# regulateur.net
KiCad netlist of a schematic drawn in EAGLE
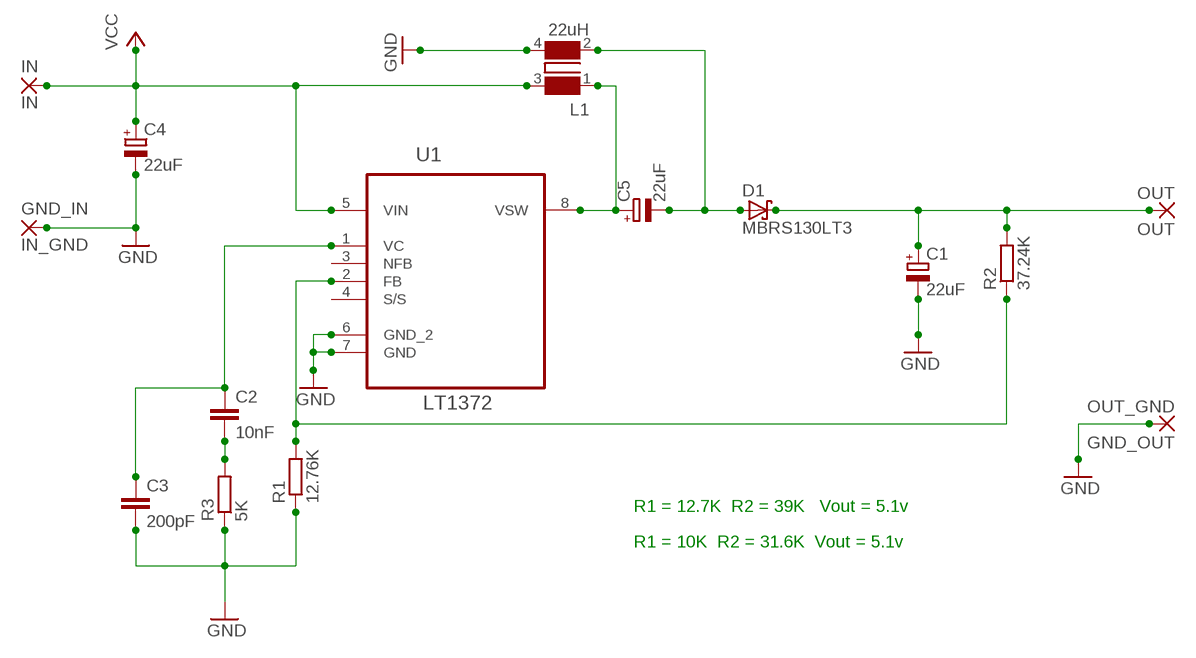
[diagram p0: schematic, sheet 1]

(export (version "E")
  (design (tool "Eeschema 10.0.6"))
  (components
    (comp (ref "C1")
      (value "22uF")
      (footprint "eagle-import:CT7343")
      (libsource (lib "eagle-import") (part "CPOL-EUCT7343"))
    )
    (comp (ref "C2")
      (value "10nF")
      (footprint "eagle-import:C1206")
      (libsource (lib "eagle-import") (part "C-EUC1206"))
    )
    (comp (ref "C3")
      (value "200pF")
      (footprint "eagle-import:C1206")
      (libsource (lib "eagle-import") (part "C-EUC1206"))
    )
    (comp (ref "C4")
      (value "22uF")
      (footprint "eagle-import:CT7343")
      (libsource (lib "eagle-import") (part "CPOL-EUCT7343"))
    )
    (comp (ref "C5")
      (value "22uF")
      (footprint "eagle-import:CT7343")
      (libsource (lib "eagle-import") (part "CPOL-EUCT7343"))
    )
    (comp (ref "D1")
      (value "MBRS130LT3")
      (footprint "eagle-import:SMB")
      (libsource (lib "eagle-import") (part "MBRS130LT3"))
    )
    (comp (ref "GND_IN")
      (value "IN_GND")
      (footprint "eagle-import:3,81_1,3")
      (libsource (lib "eagle-import") (part "3,81/1,3"))
    )
    (comp (ref "GND_OUT")
      (value "OUT_GND")
      (footprint "eagle-import:3,81_1,3")
      (libsource (lib "eagle-import") (part "3,81/1,3"))
    )
    (comp (ref "IN")
      (value "IN")
      (footprint "eagle-import:3,81_1,3")
      (libsource (lib "eagle-import") (part "3,81/1,3"))
    )
    (comp (ref "L1")
      (value "22uH")
      (footprint "eagle-import:WE-DD_12XX_CROSSED")
      (fields (field (name "MPN") "744871220"))
      (libsource (lib "eagle-import") (part "WE-DD_1260/1280/1210_CROSSED-744871220"))
    )
    (comp (ref "OUT")
      (value "OUT")
      (footprint "eagle-import:3,81_1,3")
      (libsource (lib "eagle-import") (part "3,81/1,3"))
    )
    (comp (ref "R1")
      (value "12.76K")
      (footprint "eagle-import:M1206")
      (libsource (lib "eagle-import") (part "R-EU_M1206"))
    )
    (comp (ref "R2")
      (value "37.24K")
      (footprint "eagle-import:M1206")
      (libsource (lib "eagle-import") (part "R-EU_M1206"))
    )
    (comp (ref "R3")
      (value "5K")
      (footprint "eagle-import:M1206")
      (libsource (lib "eagle-import") (part "R-EU_M1206"))
    )
    (comp (ref "U1")
      (value "LT1372")
      (footprint "eagle-import:SOIC127P600X175-8N")
      (fields (field (name "MPN") "LT1372CS8#PBF"))
      (libsource (lib "eagle-import") (part "LT1372CS8PBF"))
    )
  )
  (nets
    (net (code "1") (name "GND") (class "Default")
      (node (ref "C1") (pin "-") (pinfunction "-_-") (pintype "passive"))
      (node (ref "C3") (pin "2") (pinfunction "2_2") (pintype "passive"))
      (node (ref "C4") (pin "-") (pinfunction "-_-") (pintype "passive"))
      (node (ref "GND_IN") (pin "1") (pinfunction "P_1") (pintype "passive"))
      (node (ref "GND_OUT") (pin "1") (pinfunction "P_1") (pintype "passive"))
      (node (ref "L1") (pin "4") (pinfunction "2_4") (pintype "passive"))
      (node (ref "R1") (pin "1") (pinfunction "1_1") (pintype "passive"))
      (node (ref "R3") (pin "1") (pinfunction "1_1") (pintype "passive"))
      (node (ref "U1") (pin "6") (pinfunction "GND_2_6") (pintype "passive"))
      (node (ref "U1") (pin "7") (pinfunction "GND_7") (pintype "passive"))
    )
    (net (code "2") (name "Net-(C2-Pad2)") (class "Default")
      (node (ref "C2") (pin "2") (pinfunction "2_2") (pintype "passive"))
      (node (ref "R3") (pin "2") (pinfunction "2_2") (pintype "passive"))
    )
    (net (code "3") (name "Net-(L1-1)") (class "Default")
      (node (ref "C5") (pin "-") (pinfunction "-_-") (pintype "passive"))
      (node (ref "D1") (pin "A") (pinfunction "A_A") (pintype "passive"))
      (node (ref "L1") (pin "2") (pinfunction "1_2") (pintype "passive"))
    )
    (net (code "4") (name "Net-(L1-3)") (class "Default")
      (node (ref "C5") (pin "+") (pinfunction "+_+") (pintype "passive"))
      (node (ref "L1") (pin "1") (pinfunction "3_1") (pintype "passive"))
      (node (ref "U1") (pin "8") (pinfunction "VSW_8") (pintype "output"))
    )
    (net (code "5") (name "Net-(OUT-P)") (class "Default")
      (node (ref "C1") (pin "+") (pinfunction "+_+") (pintype "passive"))
      (node (ref "D1") (pin "C") (pinfunction "C_C") (pintype "passive"))
      (node (ref "OUT") (pin "1") (pinfunction "P_1") (pintype "passive"))
      (node (ref "R2") (pin "2") (pinfunction "2_2") (pintype "passive"))
    )
    (net (code "6") (name "Net-(U1-FB)") (class "Default")
      (node (ref "R1") (pin "2") (pinfunction "2_2") (pintype "passive"))
      (node (ref "R2") (pin "1") (pinfunction "1_1") (pintype "passive"))
      (node (ref "U1") (pin "2") (pinfunction "FB_2") (pintype "input"))
    )
    (net (code "7") (name "Net-(U1-VC)") (class "Default")
      (node (ref "C2") (pin "1") (pinfunction "1_1") (pintype "passive"))
      (node (ref "C3") (pin "1") (pinfunction "1_1") (pintype "passive"))
      (node (ref "U1") (pin "1") (pinfunction "VC_1") (pintype "input"))
    )
    (net (code "8") (name "VCC") (class "Default")
      (node (ref "C4") (pin "+") (pinfunction "+_+") (pintype "passive"))
      (node (ref "IN") (pin "1") (pinfunction "P_1") (pintype "passive"))
      (node (ref "L1") (pin "3") (pinfunction "4_3") (pintype "passive"))
      (node (ref "U1") (pin "5") (pinfunction "VIN_5") (pintype "power_in"))
    )
    (net (code "9") (name "unconnected-(U1-NFB-Pad3)") (class "Default")
      (node (ref "U1") (pin "3") (pinfunction "NFB_3") (pintype "input"))
    )
    (net (code "10") (name "unconnected-(U1-S{slash}S-Pad4)") (class "Default")
      (node (ref "U1") (pin "4") (pinfunction "S/S_4") (pintype "input"))
    )
  )
)
